# Headband_Board.net
KiCad netlist of a schematic drawn in EAGLE
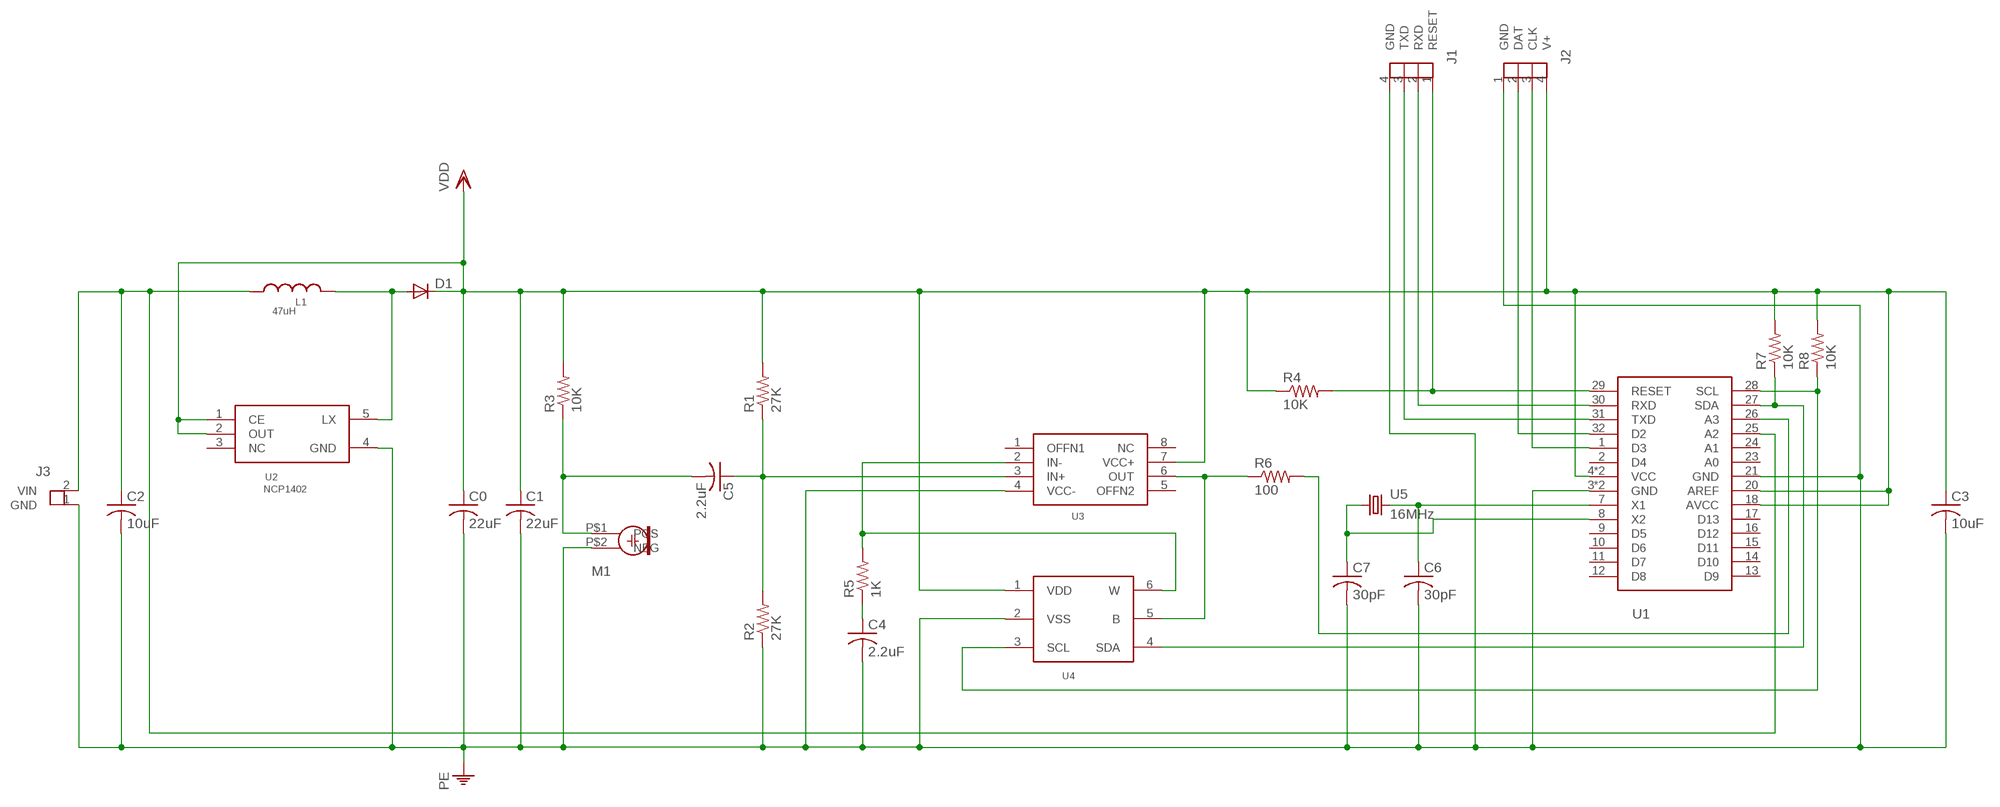
[diagram p0: schematic, sheet 1]

(export (version "E")
  (design (tool "Eeschema 10.0.6"))
  (components
    (comp (ref "C0")
      (value "22uF")
      (footprint "eagle-import:0805")
      (libsource (lib "eagle-import") (part "CAP0805"))
    )
    (comp (ref "C1")
      (value "22uF")
      (footprint "eagle-import:0805")
      (libsource (lib "eagle-import") (part "CAP0805"))
    )
    (comp (ref "C2")
      (value "10uF")
      (footprint "eagle-import:0805")
      (libsource (lib "eagle-import") (part "CAP0805"))
    )
    (comp (ref "C3")
      (value "10uF")
      (footprint "eagle-import:0805")
      (libsource (lib "eagle-import") (part "CAP0805"))
    )
    (comp (ref "C4")
      (value "2.2uF")
      (footprint "eagle-import:0603")
      (libsource (lib "eagle-import") (part "CAP0603"))
    )
    (comp (ref "C5")
      (value "2.2uF")
      (footprint "eagle-import:0603")
      (libsource (lib "eagle-import") (part "CAP0603"))
    )
    (comp (ref "C6")
      (value "30pF")
      (footprint "eagle-import:0603")
      (libsource (lib "eagle-import") (part "CAP0603"))
    )
    (comp (ref "C7")
      (value "30pF")
      (footprint "eagle-import:0603")
      (libsource (lib "eagle-import") (part "CAP0603"))
    )
    (comp (ref "D1")
      (value "MBR0520LT")
      (footprint "eagle-import:SOD-123")
      (libsource (lib "eagle-import") (part "MBR0520LT"))
    )
    (comp (ref "J1")
      (value "PRGMCONN")
      (footprint "eagle-import:4CONN")
      (libsource (lib "eagle-import") (part "PRGMCONN"))
    )
    (comp (ref "J2")
      (value "LEDCONN")
      (footprint "eagle-import:4CONN")
      (libsource (lib "eagle-import") (part "LEDCONN"))
    )
    (comp (ref "J3")
      (value "PWRCONN")
      (footprint "eagle-import:2CONN")
      (libsource (lib "eagle-import") (part "PWRCONN"))
    )
    (comp (ref "L1")
      (value "47uH")
      (footprint "eagle-import:INDUCPAC")
      (libsource (lib "eagle-import") (part "CBC2518"))
    )
    (comp (ref "M1")
      (value "ELEC_MIC")
      (footprint "eagle-import:ELEC_MIC")
      (libsource (lib "eagle-import") (part "ELEC_MIC"))
    )
    (comp (ref "R1")
      (value "27K")
      (footprint "eagle-import:0603")
      (libsource (lib "eagle-import") (part "RESISTOR"))
    )
    (comp (ref "R2")
      (value "27K")
      (footprint "eagle-import:0603")
      (libsource (lib "eagle-import") (part "RESISTOR"))
    )
    (comp (ref "R3")
      (value "10K")
      (footprint "eagle-import:0603")
      (libsource (lib "eagle-import") (part "RESISTOR"))
    )
    (comp (ref "R4")
      (value "10K")
      (footprint "eagle-import:0603")
      (libsource (lib "eagle-import") (part "RESISTOR"))
    )
    (comp (ref "R5")
      (value "1K")
      (footprint "eagle-import:0603")
      (libsource (lib "eagle-import") (part "RESISTOR"))
    )
    (comp (ref "R6")
      (value "100")
      (footprint "eagle-import:0603")
      (libsource (lib "eagle-import") (part "RESISTOR"))
    )
    (comp (ref "R7")
      (value "10K")
      (footprint "eagle-import:0603")
      (libsource (lib "eagle-import") (part "RESISTOR"))
    )
    (comp (ref "R8")
      (value "10K")
      (footprint "eagle-import:0603")
      (libsource (lib "eagle-import") (part "RESISTOR"))
    )
    (comp (ref "U1")
      (value "ATMEGA328P")
      (footprint "eagle-import:TQFP32-08")
      (libsource (lib "eagle-import") (part "ATMEGA328P"))
    )
    (comp (ref "U2")
      (value "NCP1402")
      (footprint "eagle-import:TSOT-23-5")
      (libsource (lib "eagle-import") (part "NCP1402"))
    )
    (comp (ref "U3")
      (value "TL071")
      (footprint "eagle-import:8-SOIC")
      (libsource (lib "eagle-import") (part "TL071"))
    )
    (comp (ref "U4")
      (value "MCP4017")
      (footprint "eagle-import:SOT-363")
      (libsource (lib "eagle-import") (part "MCP4017"))
    )
    (comp (ref "U5")
      (value "16MHz")
      (footprint "eagle-import:HC49_US")
      (libsource (lib "eagle-import") (part "CRYSTAL"))
    )
  )
  (nets
    (net (code "1") (name "Net-(C2-1)") (class "Default")
      (node (ref "C2") (pin "A") (pinfunction "1_A") (pintype "passive"))
      (node (ref "J3") (pin "2") (pinfunction "VIN_2") (pintype "bidirectional"))
      (node (ref "L1") (pin "3.7X1.2") (pinfunction "1_3.7X1.2") (pintype "passive"))
      (node (ref "U1") (pin "25") (pinfunction "A2_25") (pintype "bidirectional"))
    )
    (net (code "2") (name "Net-(C4-Pad1)") (class "Default")
      (node (ref "C4") (pin "1") (pinfunction "1_1") (pintype "passive"))
      (node (ref "R5") (pin "1") (pinfunction "1_1") (pintype "passive"))
    )
    (net (code "3") (name "Net-(J1-RESET)") (class "Default")
      (node (ref "J1") (pin "1") (pinfunction "RESET_1") (pintype "bidirectional"))
      (node (ref "R4") (pin "2") (pinfunction "2_2") (pintype "passive"))
      (node (ref "U1") (pin "29") (pinfunction "RESET_29") (pintype "bidirectional"))
    )
    (net (code "4") (name "Net-(J1-RXD)") (class "Default")
      (node (ref "J1") (pin "2") (pinfunction "RXD_2") (pintype "bidirectional"))
      (node (ref "U1") (pin "30") (pinfunction "RXD_30") (pintype "bidirectional"))
    )
    (net (code "5") (name "Net-(J1-TXD)") (class "Default")
      (node (ref "J1") (pin "3") (pinfunction "TXD_3") (pintype "bidirectional"))
      (node (ref "U1") (pin "31") (pinfunction "TXD_31") (pintype "bidirectional"))
    )
    (net (code "6") (name "Net-(J2-CLK)") (class "Default")
      (node (ref "J2") (pin "3") (pinfunction "CLK_3") (pintype "bidirectional"))
      (node (ref "U1") (pin "1") (pinfunction "D3_1") (pintype "bidirectional"))
    )
    (net (code "7") (name "Net-(J2-DAT)") (class "Default")
      (node (ref "J2") (pin "2") (pinfunction "DAT_2") (pintype "bidirectional"))
      (node (ref "U1") (pin "32") (pinfunction "D2_32") (pintype "bidirectional"))
    )
    (net (code "8") (name "Net-(M1-POS)") (class "Default")
      (node (ref "C5") (pin "2") (pinfunction "2_2") (pintype "passive"))
      (node (ref "M1") (pin "P$1") (pinfunction "POS_P$1") (pintype "passive"))
      (node (ref "R3") (pin "1") (pinfunction "1_1") (pintype "passive"))
    )
    (net (code "9") (name "Net-(U1-A3)") (class "Default")
      (node (ref "R6") (pin "2") (pinfunction "2_2") (pintype "passive"))
      (node (ref "U1") (pin "26") (pinfunction "A3_26") (pintype "bidirectional"))
    )
    (net (code "10") (name "Net-(U1-SCL)") (class "Default")
      (node (ref "R8") (pin "1") (pinfunction "1_1") (pintype "passive"))
      (node (ref "U1") (pin "28") (pinfunction "SCL_28") (pintype "bidirectional"))
      (node (ref "U4") (pin "3") (pinfunction "SCL_3") (pintype "bidirectional"))
    )
    (net (code "11") (name "Net-(U1-SDA)") (class "Default")
      (node (ref "R7") (pin "1") (pinfunction "1_1") (pintype "passive"))
      (node (ref "U1") (pin "27") (pinfunction "SDA_27") (pintype "bidirectional"))
      (node (ref "U4") (pin "4") (pinfunction "SDA_4") (pintype "bidirectional"))
    )
    (net (code "12") (name "Net-(U1-X1)") (class "Default")
      (node (ref "C6") (pin "1") (pinfunction "1_1") (pintype "passive"))
      (node (ref "U1") (pin "7") (pinfunction "X1_7") (pintype "bidirectional"))
      (node (ref "U5") (pin "P$2") (pinfunction "2_P$2") (pintype "passive"))
    )
    (net (code "13") (name "Net-(U1-X2)") (class "Default")
      (node (ref "C7") (pin "1") (pinfunction "1_1") (pintype "passive"))
      (node (ref "U1") (pin "8") (pinfunction "X2_8") (pintype "bidirectional"))
      (node (ref "U5") (pin "P$1") (pinfunction "1_P$1") (pintype "passive"))
    )
    (net (code "14") (name "Net-(U2-LX)") (class "Default")
      (node (ref "D1") (pin "A") (pinfunction "A_A") (pintype "passive"))
      (node (ref "L1") (pin "2") (pinfunction "2_2") (pintype "passive"))
      (node (ref "U2") (pin "5") (pinfunction "LX_5") (pintype "bidirectional"))
    )
    (net (code "15") (name "Net-(U3-IN+)") (class "Default")
      (node (ref "C5") (pin "1") (pinfunction "1_1") (pintype "passive"))
      (node (ref "R1") (pin "1") (pinfunction "1_1") (pintype "passive"))
      (node (ref "R2") (pin "2") (pinfunction "2_2") (pintype "passive"))
      (node (ref "U3") (pin "3") (pinfunction "IN+_3") (pintype "bidirectional"))
    )
    (net (code "16") (name "Net-(U3-IN-)") (class "Default")
      (node (ref "R5") (pin "2") (pinfunction "2_2") (pintype "passive"))
      (node (ref "U3") (pin "2") (pinfunction "IN-_2") (pintype "bidirectional"))
      (node (ref "U4") (pin "6") (pinfunction "W_6") (pintype "bidirectional"))
    )
    (net (code "17") (name "Net-(U3-OUT)") (class "Default")
      (node (ref "R6") (pin "1") (pinfunction "1_1") (pintype "passive"))
      (node (ref "U3") (pin "6") (pinfunction "OUT_6") (pintype "bidirectional"))
      (node (ref "U4") (pin "5") (pinfunction "B_5") (pintype "bidirectional"))
    )
    (net (code "18") (name "PE") (class "Default")
      (node (ref "C0") (pin "A1") (pinfunction "2_A1") (pintype "passive"))
      (node (ref "C1") (pin "A1") (pinfunction "2_A1") (pintype "passive"))
      (node (ref "C2") (pin "A1") (pinfunction "2_A1") (pintype "passive"))
      (node (ref "C3") (pin "A1") (pinfunction "2_A1") (pintype "passive"))
      (node (ref "C4") (pin "2") (pinfunction "2_2") (pintype "passive"))
      (node (ref "C6") (pin "2") (pinfunction "2_2") (pintype "passive"))
      (node (ref "C7") (pin "2") (pinfunction "2_2") (pintype "passive"))
      (node (ref "J1") (pin "4") (pinfunction "GND_4") (pintype "bidirectional"))
      (node (ref "J2") (pin "1") (pinfunction "GND_1") (pintype "bidirectional"))
      (node (ref "J3") (pin "1") (pinfunction "GND_1") (pintype "bidirectional"))
      (node (ref "M1") (pin "P$2") (pinfunction "NEG_P$2") (pintype "passive"))
      (node (ref "R2") (pin "1") (pinfunction "1_1") (pintype "passive"))
      (node (ref "U1") (pin "21") (pinfunction "GND_21") (pintype "bidirectional"))
      (node (ref "U1") (pin "3") (pinfunction "GND_3") (pintype "bidirectional"))
      (node (ref "U1") (pin "5") (pinfunction "GND_5") (pintype "bidirectional"))
      (node (ref "U2") (pin "4") (pinfunction "GND_4") (pintype "bidirectional"))
      (node (ref "U3") (pin "4") (pinfunction "VCC-_4") (pintype "bidirectional"))
      (node (ref "U4") (pin "2") (pinfunction "VSS_2") (pintype "bidirectional"))
    )
    (net (code "19") (name "VDD") (class "Default")
      (node (ref "C0") (pin "A") (pinfunction "1_A") (pintype "passive"))
      (node (ref "C1") (pin "A") (pinfunction "1_A") (pintype "passive"))
      (node (ref "C3") (pin "A") (pinfunction "1_A") (pintype "passive"))
      (node (ref "D1") (pin "B") (pinfunction "B_B") (pintype "passive"))
      (node (ref "J2") (pin "4") (pinfunction "V+_4") (pintype "bidirectional"))
      (node (ref "R1") (pin "2") (pinfunction "2_2") (pintype "passive"))
      (node (ref "R3") (pin "2") (pinfunction "2_2") (pintype "passive"))
      (node (ref "R4") (pin "1") (pinfunction "1_1") (pintype "passive"))
      (node (ref "R7") (pin "2") (pinfunction "2_2") (pintype "passive"))
      (node (ref "R8") (pin "2") (pinfunction "2_2") (pintype "passive"))
      (node (ref "U1") (pin "18") (pinfunction "AVCC_18") (pintype "bidirectional"))
      (node (ref "U1") (pin "20") (pinfunction "AREF_20") (pintype "bidirectional"))
      (node (ref "U1") (pin "4") (pinfunction "VCC_4") (pintype "bidirectional"))
      (node (ref "U1") (pin "6") (pinfunction "VCC_6") (pintype "bidirectional"))
      (node (ref "U2") (pin "1") (pinfunction "CE_1") (pintype "bidirectional"))
      (node (ref "U2") (pin "2") (pinfunction "OUT_2") (pintype "bidirectional"))
      (node (ref "U3") (pin "7") (pinfunction "VCC+_7") (pintype "bidirectional"))
      (node (ref "U4") (pin "1") (pinfunction "VDD_1") (pintype "bidirectional"))
    )
    (net (code "20") (name "unconnected-(U1-A0-Pad23)") (class "Default")
      (node (ref "U1") (pin "23") (pinfunction "A0_23") (pintype "bidirectional"))
    )
    (net (code "21") (name "unconnected-(U1-A1-Pad24)") (class "Default")
      (node (ref "U1") (pin "24") (pinfunction "A1_24") (pintype "bidirectional"))
    )
    (net (code "22") (name "unconnected-(U1-D4-Pad2)") (class "Default")
      (node (ref "U1") (pin "2") (pinfunction "D4_2") (pintype "bidirectional"))
    )
    (net (code "23") (name "unconnected-(U1-D5-Pad9)") (class "Default")
      (node (ref "U1") (pin "9") (pinfunction "D5_9") (pintype "bidirectional"))
    )
    (net (code "24") (name "unconnected-(U1-D6-Pad10)") (class "Default")
      (node (ref "U1") (pin "10") (pinfunction "D6_10") (pintype "bidirectional"))
    )
    (net (code "25") (name "unconnected-(U1-D7-Pad11)") (class "Default")
      (node (ref "U1") (pin "11") (pinfunction "D7_11") (pintype "bidirectional"))
    )
    (net (code "26") (name "unconnected-(U1-D8-Pad12)") (class "Default")
      (node (ref "U1") (pin "12") (pinfunction "D8_12") (pintype "bidirectional"))
    )
    (net (code "27") (name "unconnected-(U1-D9-Pad13)") (class "Default")
      (node (ref "U1") (pin "13") (pinfunction "D9_13") (pintype "bidirectional"))
    )
    (net (code "28") (name "unconnected-(U1-D10-Pad14)") (class "Default")
      (node (ref "U1") (pin "14") (pinfunction "D10_14") (pintype "bidirectional"))
    )
    (net (code "29") (name "unconnected-(U1-D11-Pad15)") (class "Default")
      (node (ref "U1") (pin "15") (pinfunction "D11_15") (pintype "bidirectional"))
    )
    (net (code "30") (name "unconnected-(U1-D12-Pad16)") (class "Default")
      (node (ref "U1") (pin "16") (pinfunction "D12_16") (pintype "bidirectional"))
    )
    (net (code "31") (name "unconnected-(U1-D13-Pad17)") (class "Default")
      (node (ref "U1") (pin "17") (pinfunction "D13_17") (pintype "bidirectional"))
    )
    (net (code "32") (name "unconnected-(U2-NC-Pad3)") (class "Default")
      (node (ref "U2") (pin "3") (pinfunction "NC_3") (pintype "bidirectional"))
    )
    (net (code "33") (name "unconnected-(U3-NC-Pad8)") (class "Default")
      (node (ref "U3") (pin "8") (pinfunction "NC_8") (pintype "bidirectional"))
    )
    (net (code "34") (name "unconnected-(U3-OFFN1-Pad1)") (class "Default")
      (node (ref "U3") (pin "1") (pinfunction "OFFN1_1") (pintype "bidirectional"))
    )
    (net (code "35") (name "unconnected-(U3-OFFN2-Pad5)") (class "Default")
      (node (ref "U3") (pin "5") (pinfunction "OFFN2_5") (pintype "bidirectional"))
    )
  )
)
